# BMS_AFE_-_AFE.net
KiCad netlist of a schematic drawn in Altium Designer
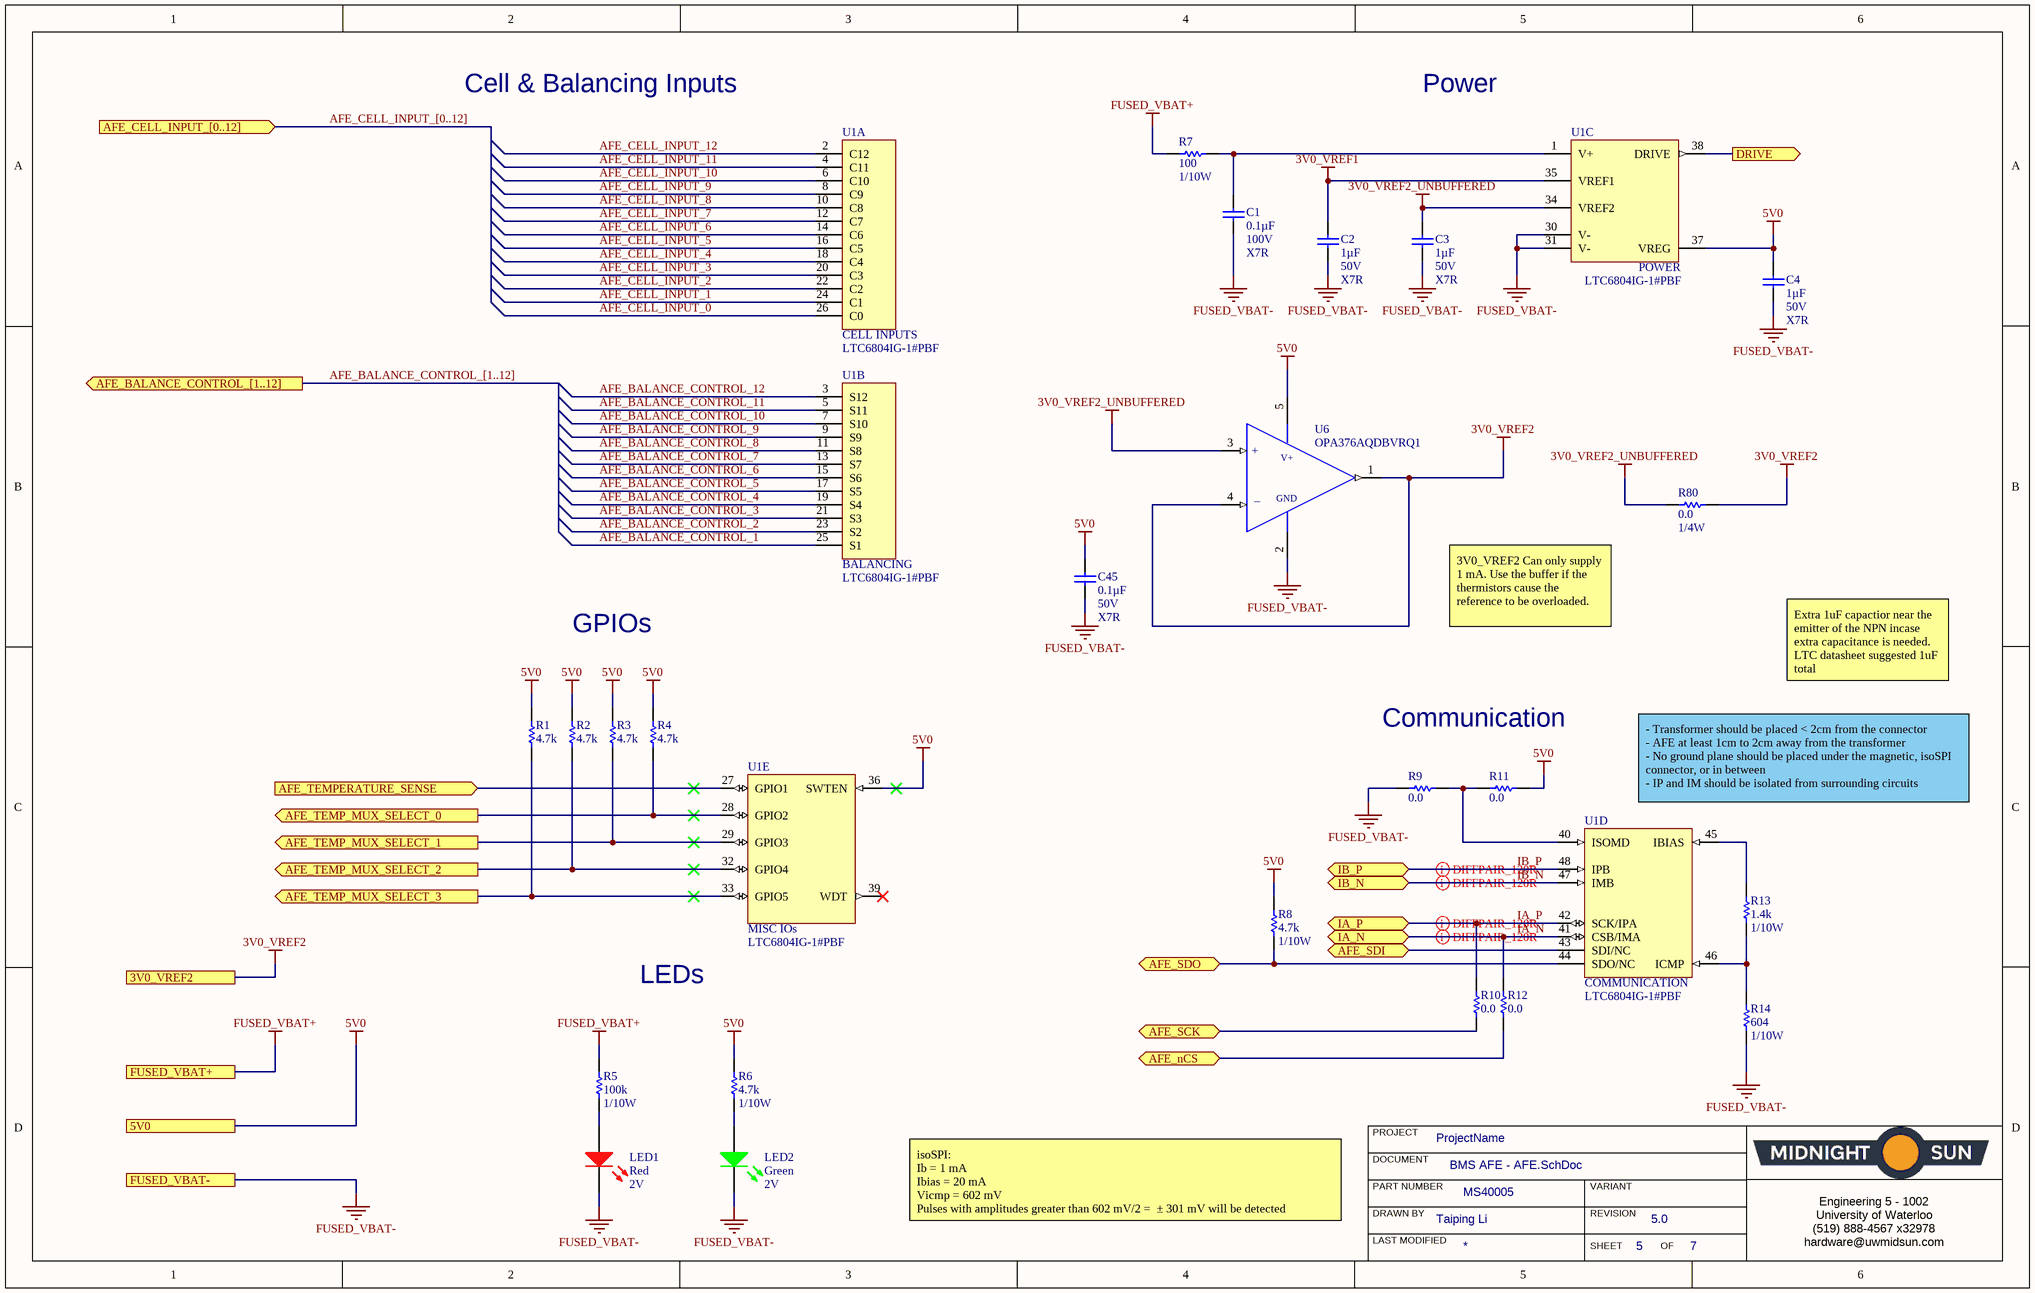
[diagram p0: BMS AFE - AFE.SchDoc]

(export (version "E")
  (design (tool "Eeschema 10.0.6"))
  (components
    (comp (ref "C1")
      (value "CAP CER 0.1UF 100V 10% X7R 0805")
      (footprint "CAP, 0805")
      (description "0.1µF ±10% 100V Ceramic Capacitor X7R 0805 (2012 Metric)")
      (fields
        (field (name "TOLERANCE") "±10%")
        (field (name "CAPACITANCE") "0.1µF")
        (field (name "VOLTAGE") "100V")
        (field (name "TEMPERATURE COEFFICIENT") "X7R")
      )
      (libsource (lib "Schematic Diagrams") (part "CAP CER 0.1UF 100V 10% X7R 0805"))
    )
    (comp (ref "C2")
      (value "CAP CER 1UF 50V 10% X7R 0603")
      (footprint "CAP, 0603")
      (description "1µF ±10% 50V Ceramic Capacitor X7R 0603 (1608 Metric)")
      (fields
        (field (name "TOLERANCE") "±10%")
        (field (name "CAPACITANCE") "1µF")
        (field (name "VOLTAGE") "50V")
        (field (name "TEMPERATURE COEFFICIENT") "X7R")
      )
      (libsource (lib "Schematic Diagrams") (part "CAP CER 1UF 50V 10% X7R 0603"))
    )
    (comp (ref "C3")
      (value "CAP CER 1UF 50V 10% X7R 0603")
      (footprint "CAP, 0603")
      (description "1µF ±10% 50V Ceramic Capacitor X7R 0603 (1608 Metric)")
      (fields
        (field (name "TOLERANCE") "±10%")
        (field (name "CAPACITANCE") "1µF")
        (field (name "VOLTAGE") "50V")
        (field (name "TEMPERATURE COEFFICIENT") "X7R")
      )
      (libsource (lib "Schematic Diagrams") (part "CAP CER 1UF 50V 10% X7R 0603"))
    )
    (comp (ref "C4")
      (value "CAP CER 1UF 50V 10% X7R 0603")
      (footprint "CAP, 0603")
      (description "1µF ±10% 50V Ceramic Capacitor X7R 0603 (1608 Metric)")
      (fields
        (field (name "TOLERANCE") "±10%")
        (field (name "CAPACITANCE") "1µF")
        (field (name "VOLTAGE") "50V")
        (field (name "TEMPERATURE COEFFICIENT") "X7R")
      )
      (libsource (lib "Schematic Diagrams") (part "CAP CER 1UF 50V 10% X7R 0603"))
    )
    (comp (ref "C45")
      (value "CAP CER 0.1UF 50V 10% X7R 0603")
      (footprint "CAP, 0603")
      (description "0.10µF ±10% 50V Ceramic Capacitor X7R 0603 (1608 Metric)")
      (fields
        (field (name "TOLERANCE") "±10%")
        (field (name "CAPACITANCE") "0.1µF")
        (field (name "VOLTAGE") "50V")
        (field (name "TEMPERATURE COEFFICIENT") "X7R")
      )
      (libsource (lib "Schematic Diagrams") (part "CAP CER 0.1UF 50V 10% X7R 0603"))
    )
    (comp (ref "LED1")
      (value "LED RED CLEAR 2V 0603")
      (footprint "LED_0603")
      (description "Red 631nm LED Indication - Discrete 2V 0603 (1608 Metric)")
      (fields
        (field (name "MANUFACTURER") "Wurth Electronics Inc.")
        (field (name "MANUFACTURER PART NUMBER") "150060RS75000")
        (field (name "COLOR") "Red")
        (field (name "VOLTAGE - FORWARD (VF) (TYP)") "2V")
      )
      (libsource (lib "Schematic Diagrams") (part "LED RED CLEAR 2V 0603"))
    )
    (comp (ref "LED2")
      (value "LED GREEN CLEAR 2V 0603")
      (footprint "LED_0603")
      (description "Green 572nm LED Indication - Discrete 2V 0603 (1608 Metric)")
      (fields
        (field (name "MANUFACTURER") "Wurth Electronics Inc.")
        (field (name "MANUFACTURER PART NUMBER") "150060VS75000")
        (field (name "COLOR") "Green")
        (field (name "VOLTAGE - FORWARD (VF) (TYP)") "2V")
      )
      (libsource (lib "Schematic Diagrams") (part "LED GREEN CLEAR 2V 0603"))
    )
    (comp (ref "R1")
      (value "RES 4.7K OHM 1% 1/10W 0603")
      (footprint "RES, 0603")
      (description "4.7k Ohm ±1% 0.1W, 1/10W Chip Resistor 0603 (1608 Metric) Moisture Resistant Thick Film")
      (fields (field (name "TOLERANCE") "±1%") (field (name "RESISTANCE (OHMS)") "4.7k"))
      (libsource (lib "Schematic Diagrams") (part "RES 4.7K OHM 1% 1/10W 0603"))
    )
    (comp (ref "R2")
      (value "RES 4.7K OHM 1% 1/10W 0603")
      (footprint "RES, 0603")
      (description "4.7k Ohm ±1% 0.1W, 1/10W Chip Resistor 0603 (1608 Metric) Moisture Resistant Thick Film")
      (fields (field (name "TOLERANCE") "±1%") (field (name "RESISTANCE (OHMS)") "4.7k"))
      (libsource (lib "Schematic Diagrams") (part "RES 4.7K OHM 1% 1/10W 0603"))
    )
    (comp (ref "R3")
      (value "RES 4.7K OHM 1% 1/10W 0603")
      (footprint "RES, 0603")
      (description "4.7k Ohm ±1% 0.1W, 1/10W Chip Resistor 0603 (1608 Metric) Moisture Resistant Thick Film")
      (fields (field (name "TOLERANCE") "±1%") (field (name "RESISTANCE (OHMS)") "4.7k"))
      (libsource (lib "Schematic Diagrams") (part "RES 4.7K OHM 1% 1/10W 0603"))
    )
    (comp (ref "R4")
      (value "RES 4.7K OHM 1% 1/10W 0603")
      (footprint "RES, 0603")
      (description "4.7k Ohm ±1% 0.1W, 1/10W Chip Resistor 0603 (1608 Metric) Moisture Resistant Thick Film")
      (fields (field (name "TOLERANCE") "±1%") (field (name "RESISTANCE (OHMS)") "4.7k"))
      (libsource (lib "Schematic Diagrams") (part "RES 4.7K OHM 1% 1/10W 0603"))
    )
    (comp (ref "R5")
      (value "RES 100K OHM 5% 1/8W 0603")
      (footprint "RES, 0603")
      (description "RES SMD 100K OHM 5% 1/10W 0603")
      (fields
        (field (name "TOLERANCE") "±5%")
        (field (name "RESISTANCE") "100k")
        (field (name "POWER") "1/10W")
      )
      (libsource (lib "Schematic Diagrams") (part "RES 100K OHM 5% 1/8W 0603"))
    )
    (comp (ref "R6")
      (value "RES 4.7K OHM 1% 1/10W 0603")
      (footprint "RES, 0603")
      (description "4.7k Ohm ±1% 0.1W, 1/10W Chip Resistor 0603 (1608 Metric) Moisture Resistant Thick Film")
      (fields
        (field (name "TOLERANCE") "±1%")
        (field (name "RESISTANCE (OHMS)") "4.7k")
        (field (name "POWER (WATTS)") "1/10W")
      )
      (libsource (lib "Schematic Diagrams") (part "RES 4.7K OHM 1% 1/10W 0603"))
    )
    (comp (ref "R7")
      (value "RES 100 OHM 1% 1/10W 0603")
      (footprint "RES, 0603")
      (description "100 Ohm ±1% 0.1W, 1/10W Chip Resistor 0603 (1608 Metric) Moisture Resistant Thick Film")
      (fields
        (field (name "TOLERANCE") "±1%")
        (field (name "RESISTANCE") "100")
        (field (name "POWER") "1/10W")
      )
      (libsource (lib "Schematic Diagrams") (part "RES 100 OHM 1% 1/10W 0603"))
    )
    (comp (ref "R8")
      (value "RES 4.7K OHM 1% 1/10W 0603")
      (footprint "RES, 0603")
      (description "4.7k Ohm ±1% 0.1W, 1/10W Chip Resistor 0603 (1608 Metric) Moisture Resistant Thick Film")
      (fields
        (field (name "TOLERANCE") "±1%")
        (field (name "RESISTANCE (OHMS)") "4.7k")
        (field (name "POWER (WATTS)") "1/10W")
      )
      (libsource (lib "Schematic Diagrams") (part "RES 4.7K OHM 1% 1/10W 0603"))
    )
    (comp (ref "R9")
      (value "RES 0.0 OHM 1/4W 0603")
      (footprint "RES, 0603")
      (description "RES SMD 0.0 OHM JUMPER 1/4W 0603")
      (fields (field (name "RESISTANCE") "0.0"))
      (libsource (lib "Schematic Diagrams") (part "RES 0.0 OHM 1/4W 0603"))
    )
    (comp (ref "R10")
      (value "RES 0.0 OHM 1/4W 0603")
      (footprint "RES, 0603")
      (description "RES SMD 0.0 OHM JUMPER 1/4W 0603")
      (fields (field (name "RESISTANCE") "0.0"))
      (libsource (lib "Schematic Diagrams") (part "RES 0.0 OHM 1/4W 0603"))
    )
    (comp (ref "R11")
      (value "RES 0.0 OHM 1/4W 0603")
      (footprint "RES, 0603")
      (description "RES SMD 0.0 OHM JUMPER 1/4W 0603")
      (fields (field (name "RESISTANCE") "0.0"))
      (libsource (lib "Schematic Diagrams") (part "RES 0.0 OHM 1/4W 0603"))
    )
    (comp (ref "R12")
      (value "RES 0.0 OHM 1/4W 0603")
      (footprint "RES, 0603")
      (description "RES SMD 0.0 OHM JUMPER 1/4W 0603")
      (fields (field (name "RESISTANCE") "0.0"))
      (libsource (lib "Schematic Diagrams") (part "RES 0.0 OHM 1/4W 0603"))
    )
    (comp (ref "R13")
      (value "RES 1.4k OHM 1% 1/10W 0603")
      (footprint "RES, 0603")
      (description "RES SMD 1.4K OHM 1% 1/10W 0603")
      (fields
        (field (name "TOLERANCE") "±1%")
        (field (name "RESISTANCE") "1.4k")
        (field (name "POWER") "1/10W")
      )
      (libsource (lib "Schematic Diagrams") (part "RES 1.4k OHM 1% 1/10W 0603"))
    )
    (comp (ref "R14")
      (value "RES 604 OHM 1% 1/10W 0603")
      (footprint "RES, 0603")
      (description "RES SMD 604 OHM 1% 1/10W 0603")
      (fields
        (field (name "TOLERANCE") "±1%")
        (field (name "RESISTANCE") "604")
        (field (name "POWER") "1/10W")
      )
      (libsource (lib "Schematic Diagrams") (part "RES 604 OHM 1% 1/10W 0603"))
    )
    (comp (ref "R80")
      (value "RES 0.0 OHM 1/4W 0603")
      (footprint "RES, 0603")
      (description "RES SMD 0.0 OHM JUMPER 1/4W 0603")
      (fields (field (name "RESISTANCE") "0.0") (field (name "POWER (WATTS)") "1/4W"))
      (libsource (lib "Schematic Diagrams") (part "RES 0.0 OHM 1/4W 0603"))
    )
    (comp (ref "U1")
      (value "IC MONITOR BATT STACK 48SSOP")
      (footprint "SSOP50P780X200-48N")
      (description "Battery Battery Monitor IC Multi-Chemistry 48-SSOP")
      (fields (field (name "MANUFACTURER PART NUMBER 1") "LTC6804IG-1#PBF"))
      (libsource (lib "Schematic Diagrams") (part "IC MONITOR BATT STACK 48SSOP"))
    )
    (comp (ref "U6")
      (value "IC OP AMP GEN PURPOSE RR 5.5MHZ SOT-23-5")
      (footprint "IC OP AMP GP RR 10MHZ SOT-23-5")
      (description "General Purpose Amplifier 1 Circuit Rail-to-Rail SOT-23-5")
      (fields
        (field (name "MANUFACTURER") "Texas Instruments")
        (field (name "MANUFACTURER PART NUMBER") "OPA376AQDBVRQ1")
      )
      (libsource (lib "Schematic Diagrams") (part "IC OP AMP GEN PURPOSE RR 5.5MHZ SOT-23-5"))
    )
  )
  (nets
    (net (code "1") (name "/AFE_BALANCE_CONTROL_1") (class "Default")
      (node (ref "U1") (pin "25") (pinfunction "S1_25") (pintype "passive"))
    )
    (net (code "2") (name "/AFE_BALANCE_CONTROL_2") (class "Default")
      (node (ref "U1") (pin "23") (pinfunction "S2_23") (pintype "passive"))
    )
    (net (code "3") (name "/AFE_BALANCE_CONTROL_3") (class "Default")
      (node (ref "U1") (pin "21") (pinfunction "S3_21") (pintype "passive"))
    )
    (net (code "4") (name "/AFE_BALANCE_CONTROL_4") (class "Default")
      (node (ref "U1") (pin "19") (pinfunction "S4_19") (pintype "passive"))
    )
    (net (code "5") (name "/AFE_BALANCE_CONTROL_5") (class "Default")
      (node (ref "U1") (pin "17") (pinfunction "S5_17") (pintype "passive"))
    )
    (net (code "6") (name "/AFE_BALANCE_CONTROL_6") (class "Default")
      (node (ref "U1") (pin "15") (pinfunction "S6_15") (pintype "passive"))
    )
    (net (code "7") (name "/AFE_BALANCE_CONTROL_7") (class "Default")
      (node (ref "U1") (pin "13") (pinfunction "S7_13") (pintype "passive"))
    )
    (net (code "8") (name "/AFE_BALANCE_CONTROL_8") (class "Default")
      (node (ref "U1") (pin "11") (pinfunction "S8_11") (pintype "passive"))
    )
    (net (code "9") (name "/AFE_BALANCE_CONTROL_9") (class "Default")
      (node (ref "U1") (pin "9") (pinfunction "S9_9") (pintype "passive"))
    )
    (net (code "10") (name "/AFE_BALANCE_CONTROL_10") (class "Default")
      (node (ref "U1") (pin "7") (pinfunction "S10_7") (pintype "passive"))
    )
    (net (code "11") (name "/AFE_BALANCE_CONTROL_11") (class "Default")
      (node (ref "U1") (pin "5") (pinfunction "S11_5") (pintype "passive"))
    )
    (net (code "12") (name "/AFE_BALANCE_CONTROL_12") (class "Default")
      (node (ref "U1") (pin "3") (pinfunction "S12_3") (pintype "passive"))
    )
    (net (code "14") (name "/AFE_CELL_INPUT_0") (class "Default")
      (node (ref "U1") (pin "26") (pinfunction "C0_26") (pintype "passive"))
    )
    (net (code "15") (name "/AFE_CELL_INPUT_1") (class "Default")
      (node (ref "U1") (pin "24") (pinfunction "C1_24") (pintype "passive"))
    )
    (net (code "16") (name "/AFE_CELL_INPUT_2") (class "Default")
      (node (ref "U1") (pin "22") (pinfunction "C2_22") (pintype "passive"))
    )
    (net (code "17") (name "/AFE_CELL_INPUT_3") (class "Default")
      (node (ref "U1") (pin "20") (pinfunction "C3_20") (pintype "passive"))
    )
    (net (code "18") (name "/AFE_CELL_INPUT_4") (class "Default")
      (node (ref "U1") (pin "18") (pinfunction "C4_18") (pintype "passive"))
    )
    (net (code "19") (name "/AFE_CELL_INPUT_5") (class "Default")
      (node (ref "U1") (pin "16") (pinfunction "C5_16") (pintype "passive"))
    )
    (net (code "20") (name "/AFE_CELL_INPUT_6") (class "Default")
      (node (ref "U1") (pin "14") (pinfunction "C6_14") (pintype "passive"))
    )
    (net (code "21") (name "/AFE_CELL_INPUT_7") (class "Default")
      (node (ref "U1") (pin "12") (pinfunction "C7_12") (pintype "passive"))
    )
    (net (code "22") (name "/AFE_CELL_INPUT_8") (class "Default")
      (node (ref "U1") (pin "10") (pinfunction "C8_10") (pintype "passive"))
    )
    (net (code "23") (name "/AFE_CELL_INPUT_9") (class "Default")
      (node (ref "U1") (pin "8") (pinfunction "C9_8") (pintype "passive"))
    )
    (net (code "24") (name "/AFE_CELL_INPUT_10") (class "Default")
      (node (ref "U1") (pin "6") (pinfunction "C10_6") (pintype "passive"))
    )
    (net (code "25") (name "/AFE_CELL_INPUT_11") (class "Default")
      (node (ref "U1") (pin "4") (pinfunction "C11_4") (pintype "passive"))
    )
    (net (code "26") (name "/AFE_CELL_INPUT_12") (class "Default")
      (node (ref "U1") (pin "2") (pinfunction "C12_2") (pintype "passive"))
    )
    (net (code "28") (name "/AFE_SCK") (class "Default")
      (node (ref "R10") (pin "2") (pinfunction "2_2") (pintype "passive"))
    )
    (net (code "29") (name "/AFE_SDI") (class "Default")
      (node (ref "U1") (pin "43") (pinfunction "SDI/NC_43") (pintype "passive"))
    )
    (net (code "30") (name "/AFE_SDO") (class "Default")
      (node (ref "R8") (pin "2") (pinfunction "2_2") (pintype "passive"))
      (node (ref "U1") (pin "44") (pinfunction "SDO/NC_44") (pintype "passive"))
    )
    (net (code "31") (name "/AFE_TEMPERATURE_SENSE") (class "Default")
      (node (ref "U1") (pin "27") (pinfunction "GPIO1_27") (pintype "bidirectional"))
    )
    (net (code "32") (name "/AFE_TEMP_MUX_SELECT_0") (class "Default")
      (node (ref "R4") (pin "1") (pinfunction "1_1") (pintype "passive"))
      (node (ref "U1") (pin "28") (pinfunction "GPIO2_28") (pintype "bidirectional"))
    )
    (net (code "33") (name "/AFE_TEMP_MUX_SELECT_1") (class "Default")
      (node (ref "R3") (pin "1") (pinfunction "1_1") (pintype "passive"))
      (node (ref "U1") (pin "29") (pinfunction "GPIO3_29") (pintype "bidirectional"))
    )
    (net (code "34") (name "/AFE_TEMP_MUX_SELECT_2") (class "Default")
      (node (ref "R2") (pin "1") (pinfunction "1_1") (pintype "passive"))
      (node (ref "U1") (pin "32") (pinfunction "GPIO4_32") (pintype "bidirectional"))
    )
    (net (code "35") (name "/AFE_TEMP_MUX_SELECT_3") (class "Default")
      (node (ref "R1") (pin "1") (pinfunction "1_1") (pintype "passive"))
      (node (ref "U1") (pin "33") (pinfunction "GPIO5_33") (pintype "bidirectional"))
    )
    (net (code "36") (name "/AFE_nCS") (class "Default")
      (node (ref "R12") (pin "2") (pinfunction "2_2") (pintype "passive"))
    )
    (net (code "37") (name "/DRIVE") (class "Default")
      (node (ref "U1") (pin "38") (pinfunction "DRIVE_38") (pintype "output"))
    )
    (net (code "38") (name "/IA_N") (class "Default")
      (node (ref "R12") (pin "1") (pinfunction "1_1") (pintype "passive"))
      (node (ref "U1") (pin "41") (pinfunction "CSB/IMA_41") (pintype "bidirectional"))
    )
    (net (code "39") (name "/IA_P") (class "Default")
      (node (ref "R10") (pin "1") (pinfunction "1_1") (pintype "passive"))
      (node (ref "U1") (pin "42") (pinfunction "SCK/IPA_42") (pintype "bidirectional"))
    )
    (net (code "40") (name "/IB_N") (class "Default")
      (node (ref "U1") (pin "47") (pinfunction "IMB_47") (pintype "input"))
    )
    (net (code "41") (name "/IB_P") (class "Default")
      (node (ref "U1") (pin "48") (pinfunction "IPB_48") (pintype "input"))
    )
    (net (code "42") (name "3V0_VREF1") (class "Default")
      (node (ref "C2") (pin "1") (pinfunction "1_1") (pintype "passive"))
      (node (ref "U1") (pin "35") (pinfunction "VREF1_35") (pintype "power_in"))
    )
    (net (code "43") (name "3V0_VREF2") (class "Default")
      (node (ref "R80") (pin "2") (pinfunction "2_2") (pintype "passive"))
      (node (ref "U6") (pin "1") (pinfunction "OUTPUT_1") (pintype "output"))
      (node (ref "U6") (pin "4") (pinfunction "-IN_4") (pintype "input"))
    )
    (net (code "44") (name "3V0_VREF2_UNBUFFERED") (class "Default")
      (node (ref "C3") (pin "1") (pinfunction "1_1") (pintype "passive"))
      (node (ref "R80") (pin "1") (pinfunction "1_1") (pintype "passive"))
      (node (ref "U1") (pin "34") (pinfunction "VREF2_34") (pintype "power_in"))
      (node (ref "U6") (pin "3") (pinfunction "+IN_3") (pintype "input"))
    )
    (net (code "45") (name "5V0") (class "Default")
      (node (ref "C4") (pin "1") (pinfunction "1_1") (pintype "passive"))
      (node (ref "C45") (pin "1") (pinfunction "1_1") (pintype "passive"))
      (node (ref "R1") (pin "2") (pinfunction "2_2") (pintype "passive"))
      (node (ref "R11") (pin "2") (pinfunction "2_2") (pintype "passive"))
      (node (ref "R2") (pin "2") (pinfunction "2_2") (pintype "passive"))
      (node (ref "R3") (pin "2") (pinfunction "2_2") (pintype "passive"))
      (node (ref "R4") (pin "2") (pinfunction "2_2") (pintype "passive"))
      (node (ref "R6") (pin "1") (pinfunction "1_1") (pintype "passive"))
      (node (ref "R8") (pin "1") (pinfunction "1_1") (pintype "passive"))
      (node (ref "U1") (pin "36") (pinfunction "SWTEN_36") (pintype "input"))
      (node (ref "U1") (pin "37") (pinfunction "VREG_37") (pintype "power_in"))
      (node (ref "U6") (pin "5") (pinfunction "VDD_5") (pintype "power_in"))
    )
    (net (code "46") (name "FUSED_VBAT+") (class "Default")
      (node (ref "R5") (pin "1") (pinfunction "1_1") (pintype "passive"))
      (node (ref "R7") (pin "1") (pinfunction "1_1") (pintype "passive"))
    )
    (net (code "47") (name "FUSED_VBAT-") (class "Default")
      (node (ref "C1") (pin "2") (pinfunction "2_2") (pintype "passive"))
      (node (ref "C2") (pin "2") (pinfunction "2_2") (pintype "passive"))
      (node (ref "C3") (pin "2") (pinfunction "2_2") (pintype "passive"))
      (node (ref "C4") (pin "2") (pinfunction "2_2") (pintype "passive"))
      (node (ref "C45") (pin "2") (pinfunction "2_2") (pintype "passive"))
      (node (ref "LED1") (pin "2") (pinfunction "K_2") (pintype "passive"))
      (node (ref "LED2") (pin "2") (pinfunction "K_2") (pintype "passive"))
      (node (ref "R14") (pin "2") (pinfunction "2_2") (pintype "passive"))
      (node (ref "R9") (pin "1") (pinfunction "1_1") (pintype "passive"))
      (node (ref "U1") (pin "30") (pinfunction "V-_30") (pintype "power_in"))
      (node (ref "U1") (pin "31") (pinfunction "V-_31") (pintype "power_in"))
      (node (ref "U6") (pin "2") (pinfunction "VSS_2") (pintype "power_in"))
    )
    (net (code "48") (name "Net-(LED1-A)") (class "Default")
      (node (ref "LED1") (pin "1") (pinfunction "A_1") (pintype "passive"))
      (node (ref "R5") (pin "2") (pinfunction "2_2") (pintype "passive"))
    )
    (net (code "49") (name "Net-(LED2-A)") (class "Default")
      (node (ref "LED2") (pin "1") (pinfunction "A_1") (pintype "passive"))
      (node (ref "R6") (pin "2") (pinfunction "2_2") (pintype "passive"))
    )
    (net (code "50") (name "Net-(U1C-V+)") (class "Default")
      (node (ref "C1") (pin "1") (pinfunction "1_1") (pintype "passive"))
      (node (ref "R7") (pin "2") (pinfunction "2_2") (pintype "passive"))
      (node (ref "U1") (pin "1") (pinfunction "V+_1") (pintype "power_in"))
    )
    (net (code "51") (name "Net-(U1D-IBIAS)") (class "Default")
      (node (ref "R13") (pin "1") (pinfunction "1_1") (pintype "passive"))
      (node (ref "U1") (pin "45") (pinfunction "IBIAS_45") (pintype "input"))
    )
    (net (code "52") (name "Net-(U1D-ICMP)") (class "Default")
      (node (ref "R13") (pin "2") (pinfunction "2_2") (pintype "passive"))
      (node (ref "R14") (pin "1") (pinfunction "1_1") (pintype "passive"))
      (node (ref "U1") (pin "46") (pinfunction "ICMP_46") (pintype "input"))
    )
    (net (code "53") (name "Net-(U1D-ISOMD)") (class "Default")
      (node (ref "R11") (pin "1") (pinfunction "1_1") (pintype "passive"))
      (node (ref "R9") (pin "2") (pinfunction "2_2") (pintype "passive"))
      (node (ref "U1") (pin "40") (pinfunction "ISOMD_40") (pintype "input"))
    )
    (net (code "54") (name "unconnected-(U1E-WDT-Pad39)") (class "Default")
      (node (ref "U1") (pin "39") (pinfunction "WDT_39") (pintype "output+no_connect"))
    )
  )
)
